# VocoreMotorShieldDRV8835.net
KiCad netlist of a schematic drawn in EAGLE
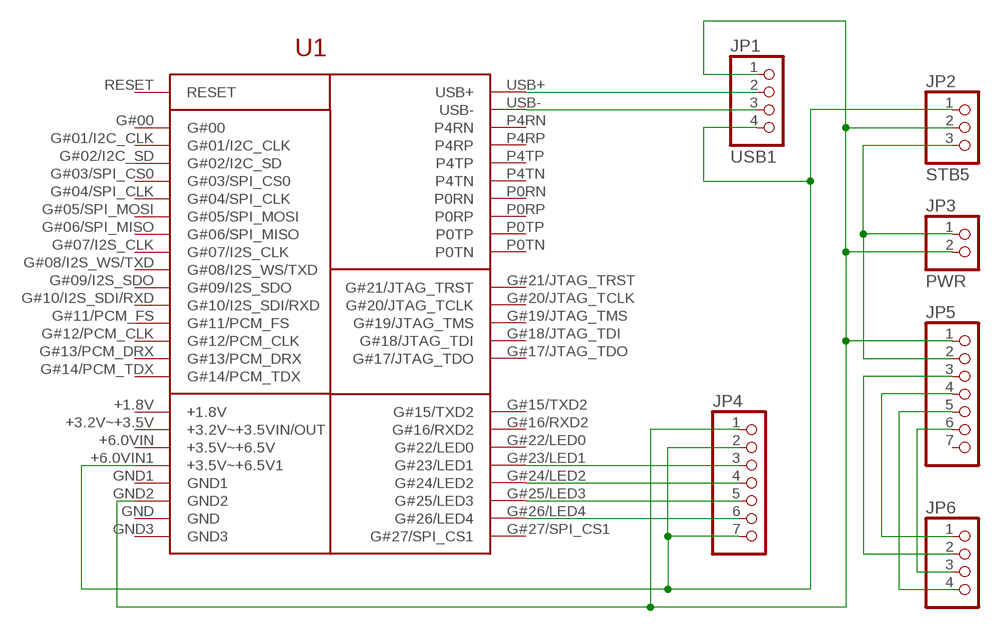
[diagram p0: schematic, sheet 1]

(export (version "E")
  (design (tool "Eeschema 10.0.6"))
  (components
    (comp (ref "JP1")
      (value "USB1")
      (footprint "eagle-import:1X04")
      (libsource (lib "eagle-import") (part "PINHD-1X4"))
    )
    (comp (ref "JP2")
      (value "STB5")
      (footprint "eagle-import:1X03")
      (libsource (lib "eagle-import") (part "PINHD-1X3"))
    )
    (comp (ref "JP3")
      (value "PWR")
      (footprint "eagle-import:1X02")
      (libsource (lib "eagle-import") (part "PINHD-1X2"))
    )
    (comp (ref "JP4")
      (value "PINHD-1X7")
      (footprint "eagle-import:1X07")
      (libsource (lib "eagle-import") (part "PINHD-1X7"))
    )
    (comp (ref "JP5")
      (value "PINHD-1X7")
      (footprint "eagle-import:1X07")
      (libsource (lib "eagle-import") (part "PINHD-1X7"))
    )
    (comp (ref "JP6")
      (value "PINHD-1X4")
      (footprint "eagle-import:1X04")
      (libsource (lib "eagle-import") (part "PINHD-1X4"))
    )
    (comp (ref "U1")
      (value "VOCORE_SHIELD")
      (footprint "eagle-import:VOCORE_DOC_CUSTOM")
      (libsource (lib "eagle-import") (part "VOCORE_SHIELD"))
    )
  )
  (nets
    (net (code "1") (name "Net-(JP1-Pad1)") (class "Default")
      (node (ref "JP1") (pin "1") (pinfunction "1_1") (pintype "passive"))
      (node (ref "JP2") (pin "2") (pinfunction "2_2") (pintype "passive"))
      (node (ref "JP3") (pin "2") (pinfunction "2_2") (pintype "passive"))
      (node (ref "JP4") (pin "1") (pinfunction "1_1") (pintype "passive"))
      (node (ref "JP5") (pin "1") (pinfunction "1_1") (pintype "passive"))
      (node (ref "U1") (pin "GND2") (pinfunction "GND2_GND2") (pintype "bidirectional"))
    )
    (net (code "2") (name "Net-(JP1-Pad2)") (class "Default")
      (node (ref "JP1") (pin "2") (pinfunction "2_2") (pintype "passive"))
      (node (ref "U1") (pin "USB+") (pinfunction "USB+_USB+") (pintype "bidirectional"))
    )
    (net (code "3") (name "Net-(JP1-Pad3)") (class "Default")
      (node (ref "JP1") (pin "3") (pinfunction "3_3") (pintype "passive"))
      (node (ref "U1") (pin "USB-") (pinfunction "USB-_USB-") (pintype "bidirectional"))
    )
    (net (code "4") (name "Net-(JP2-Pad3)") (class "Default")
      (node (ref "JP2") (pin "3") (pinfunction "3_3") (pintype "passive"))
      (node (ref "JP3") (pin "1") (pinfunction "1_1") (pintype "passive"))
      (node (ref "JP5") (pin "2") (pinfunction "2_2") (pintype "passive"))
    )
    (net (code "5") (name "Net-(JP4-Pad3)") (class "Default")
      (node (ref "JP4") (pin "3") (pinfunction "3_3") (pintype "passive"))
      (node (ref "U1") (pin "G#23/LED1") (pinfunction "G#23/LED1_G#23/LED1") (pintype "bidirectional"))
    )
    (net (code "6") (name "Net-(JP4-Pad4)") (class "Default")
      (node (ref "JP4") (pin "4") (pinfunction "4_4") (pintype "passive"))
      (node (ref "U1") (pin "G#24/LED2") (pinfunction "G#24/LED2_G#24/LED2") (pintype "bidirectional"))
    )
    (net (code "7") (name "Net-(JP4-Pad5)") (class "Default")
      (node (ref "JP4") (pin "5") (pinfunction "5_5") (pintype "passive"))
      (node (ref "U1") (pin "G#25/LED3") (pinfunction "G#25/LED3_G#25/LED3") (pintype "bidirectional"))
    )
    (net (code "8") (name "Net-(JP4-Pad6)") (class "Default")
      (node (ref "JP4") (pin "6") (pinfunction "6_6") (pintype "passive"))
      (node (ref "U1") (pin "G#26/LED4") (pinfunction "G#26/LED4_G#26/LED4") (pintype "bidirectional"))
    )
    (net (code "9") (name "Net-(JP5-Pad3)") (class "Default")
      (node (ref "JP5") (pin "3") (pinfunction "3_3") (pintype "passive"))
      (node (ref "JP6") (pin "2") (pinfunction "2_2") (pintype "passive"))
    )
    (net (code "10") (name "Net-(JP5-Pad4)") (class "Default")
      (node (ref "JP5") (pin "4") (pinfunction "4_4") (pintype "passive"))
      (node (ref "JP6") (pin "1") (pinfunction "1_1") (pintype "passive"))
    )
    (net (code "11") (name "Net-(JP5-Pad5)") (class "Default")
      (node (ref "JP5") (pin "5") (pinfunction "5_5") (pintype "passive"))
      (node (ref "JP6") (pin "4") (pinfunction "4_4") (pintype "passive"))
    )
    (net (code "12") (name "Net-(JP5-Pad6)") (class "Default")
      (node (ref "JP5") (pin "6") (pinfunction "6_6") (pintype "passive"))
      (node (ref "JP6") (pin "3") (pinfunction "3_3") (pintype "passive"))
    )
    (net (code "13") (name "Net-(U1-+3.5V~{+6.5V1})") (class "Default")
      (node (ref "JP1") (pin "4") (pinfunction "4_4") (pintype "passive"))
      (node (ref "JP2") (pin "1") (pinfunction "1_1") (pintype "passive"))
      (node (ref "JP4") (pin "2") (pinfunction "2_2") (pintype "passive"))
      (node (ref "JP4") (pin "7") (pinfunction "7_7") (pintype "passive"))
      (node (ref "U1") (pin "+6.0VIN1") (pinfunction "+3.5V~{+6.5V1}_+6.0VIN1") (pintype "bidirectional"))
    )
    (net (code "14") (name "unconnected-(JP5-Pad7)") (class "Default")
      (node (ref "JP5") (pin "7") (pinfunction "7_7") (pintype "passive"))
    )
    (net (code "15") (name "unconnected-(U1-+3.2V~{+3.5VIN{slash}OUT}-Pad+3.2V~+3.5V)") (class "Default")
      (node (ref "U1") (pin "+3.2V~+3.5V") (pinfunction "+3.2V~{+3.5VIN/OUT}_+3.2V~+3.5V") (pintype "bidirectional"))
    )
    (net (code "16") (name "unconnected-(U1-+3.5V~{+6.5V}-Pad+6.0VIN)") (class "Default")
      (node (ref "U1") (pin "+6.0VIN") (pinfunction "+3.5V~{+6.5V}_+6.0VIN") (pintype "bidirectional"))
    )
    (net (code "17") (name "unconnected-(U1-Pad+1.8V)") (class "Default")
      (node (ref "U1") (pin "+1.8V") (pinfunction "+1.8V_+1.8V") (pintype "bidirectional"))
    )
    (net (code "18") (name "unconnected-(U1-PadG#00)") (class "Default")
      (node (ref "U1") (pin "G#00") (pinfunction "G#00_G#00") (pintype "bidirectional"))
    )
    (net (code "19") (name "unconnected-(U1-PadG#01{slash}I2C_CLK)") (class "Default")
      (node (ref "U1") (pin "G#01/I2C_CLK") (pinfunction "G#01/I2C_CLK_G#01/I2C_CLK") (pintype "bidirectional"))
    )
    (net (code "20") (name "unconnected-(U1-PadG#02{slash}I2C_SD)") (class "Default")
      (node (ref "U1") (pin "G#02/I2C_SD") (pinfunction "G#02/I2C_SD_G#02/I2C_SD") (pintype "bidirectional"))
    )
    (net (code "21") (name "unconnected-(U1-PadG#03{slash}SPI_CS0)") (class "Default")
      (node (ref "U1") (pin "G#03/SPI_CS0") (pinfunction "G#03/SPI_CS0_G#03/SPI_CS0") (pintype "bidirectional"))
    )
    (net (code "22") (name "unconnected-(U1-PadG#04{slash}SPI_CLK)") (class "Default")
      (node (ref "U1") (pin "G#04/SPI_CLK") (pinfunction "G#04/SPI_CLK_G#04/SPI_CLK") (pintype "bidirectional"))
    )
    (net (code "23") (name "unconnected-(U1-PadG#05{slash}SPI_MOSI)") (class "Default")
      (node (ref "U1") (pin "G#05/SPI_MOSI") (pinfunction "G#05/SPI_MOSI_G#05/SPI_MOSI") (pintype "bidirectional"))
    )
    (net (code "24") (name "unconnected-(U1-PadG#06{slash}SPI_MISO)") (class "Default")
      (node (ref "U1") (pin "G#06/SPI_MISO") (pinfunction "G#06/SPI_MISO_G#06/SPI_MISO") (pintype "bidirectional"))
    )
    (net (code "25") (name "unconnected-(U1-PadG#07{slash}I2S_CLK)") (class "Default")
      (node (ref "U1") (pin "G#07/I2S_CLK") (pinfunction "G#07/I2S_CLK_G#07/I2S_CLK") (pintype "bidirectional"))
    )
    (net (code "26") (name "unconnected-(U1-PadG#08{slash}I2S_WS{slash}TXD)") (class "Default")
      (node (ref "U1") (pin "G#08/I2S_WS/TXD") (pinfunction "G#08/I2S_WS/TXD_G#08/I2S_WS/TXD") (pintype "bidirectional"))
    )
    (net (code "27") (name "unconnected-(U1-PadG#09{slash}I2S_SDO)") (class "Default")
      (node (ref "U1") (pin "G#09/I2S_SDO") (pinfunction "G#09/I2S_SDO_G#09/I2S_SDO") (pintype "bidirectional"))
    )
    (net (code "28") (name "unconnected-(U1-PadG#10{slash}I2S_SDI{slash}RXD)") (class "Default")
      (node (ref "U1") (pin "G#10/I2S_SDI/RXD") (pinfunction "G#10/I2S_SDI/RXD_G#10/I2S_SDI/RXD") (pintype "bidirectional"))
    )
    (net (code "29") (name "unconnected-(U1-PadG#11{slash}PCM_FS)") (class "Default")
      (node (ref "U1") (pin "G#11/PCM_FS") (pinfunction "G#11/PCM_FS_G#11/PCM_FS") (pintype "bidirectional"))
    )
    (net (code "30") (name "unconnected-(U1-PadG#12{slash}PCM_CLK)") (class "Default")
      (node (ref "U1") (pin "G#12/PCM_CLK") (pinfunction "G#12/PCM_CLK_G#12/PCM_CLK") (pintype "bidirectional"))
    )
    (net (code "31") (name "unconnected-(U1-PadG#13{slash}PCM_DRX)") (class "Default")
      (node (ref "U1") (pin "G#13/PCM_DRX") (pinfunction "G#13/PCM_DRX_G#13/PCM_DRX") (pintype "bidirectional"))
    )
    (net (code "32") (name "unconnected-(U1-PadG#14{slash}PCM_TDX)") (class "Default")
      (node (ref "U1") (pin "G#14/PCM_TDX") (pinfunction "G#14/PCM_TDX_G#14/PCM_TDX") (pintype "bidirectional"))
    )
    (net (code "33") (name "unconnected-(U1-PadG#15{slash}TXD2)") (class "Default")
      (node (ref "U1") (pin "G#15/TXD2") (pinfunction "G#15/TXD2_G#15/TXD2") (pintype "bidirectional"))
    )
    (net (code "34") (name "unconnected-(U1-PadG#16{slash}RXD2)") (class "Default")
      (node (ref "U1") (pin "G#16/RXD2") (pinfunction "G#16/RXD2_G#16/RXD2") (pintype "bidirectional"))
    )
    (net (code "35") (name "unconnected-(U1-PadG#17{slash}JTAG_TDO)") (class "Default")
      (node (ref "U1") (pin "G#17/JTAG_TDO") (pinfunction "G#17/JTAG_TDO_G#17/JTAG_TDO") (pintype "bidirectional"))
    )
    (net (code "36") (name "unconnected-(U1-PadG#18{slash}JTAG_TDI)") (class "Default")
      (node (ref "U1") (pin "G#18/JTAG_TDI") (pinfunction "G#18/JTAG_TDI_G#18/JTAG_TDI") (pintype "bidirectional"))
    )
    (net (code "37") (name "unconnected-(U1-PadG#19{slash}JTAG_TMS)") (class "Default")
      (node (ref "U1") (pin "G#19/JTAG_TMS") (pinfunction "G#19/JTAG_TMS_G#19/JTAG_TMS") (pintype "bidirectional"))
    )
    (net (code "38") (name "unconnected-(U1-PadG#20{slash}JTAG_TCLK)") (class "Default")
      (node (ref "U1") (pin "G#20/JTAG_TCLK") (pinfunction "G#20/JTAG_TCLK_G#20/JTAG_TCLK") (pintype "bidirectional"))
    )
    (net (code "39") (name "unconnected-(U1-PadG#21{slash}JTAG_TRST)") (class "Default")
      (node (ref "U1") (pin "G#21/JTAG_TRST") (pinfunction "G#21/JTAG_TRST_G#21/JTAG_TRST") (pintype "bidirectional"))
    )
    (net (code "40") (name "unconnected-(U1-PadG#22{slash}LED0)") (class "Default")
      (node (ref "U1") (pin "G#22/LED0") (pinfunction "G#22/LED0_G#22/LED0") (pintype "bidirectional"))
    )
    (net (code "41") (name "unconnected-(U1-PadG#27{slash}SPI_CS1)") (class "Default")
      (node (ref "U1") (pin "G#27/SPI_CS1") (pinfunction "G#27/SPI_CS1_G#27/SPI_CS1") (pintype "bidirectional"))
    )
    (net (code "42") (name "unconnected-(U1-PadGND)") (class "Default")
      (node (ref "U1") (pin "GND") (pinfunction "GND_GND") (pintype "bidirectional"))
    )
    (net (code "43") (name "unconnected-(U1-PadGND1)") (class "Default")
      (node (ref "U1") (pin "GND1") (pinfunction "GND1_GND1") (pintype "bidirectional"))
    )
    (net (code "44") (name "unconnected-(U1-PadGND3)") (class "Default")
      (node (ref "U1") (pin "GND3") (pinfunction "GND3_GND3") (pintype "bidirectional"))
    )
    (net (code "45") (name "unconnected-(U1-PadP0RN)") (class "Default")
      (node (ref "U1") (pin "P0RN") (pinfunction "P0RN_P0RN") (pintype "bidirectional"))
    )
    (net (code "46") (name "unconnected-(U1-PadP0RP)") (class "Default")
      (node (ref "U1") (pin "P0RP") (pinfunction "P0RP_P0RP") (pintype "bidirectional"))
    )
    (net (code "47") (name "unconnected-(U1-PadP0TN)") (class "Default")
      (node (ref "U1") (pin "P0TN") (pinfunction "P0TN_P0TN") (pintype "bidirectional"))
    )
    (net (code "48") (name "unconnected-(U1-PadP0TP)") (class "Default")
      (node (ref "U1") (pin "P0TP") (pinfunction "P0TP_P0TP") (pintype "bidirectional"))
    )
    (net (code "49") (name "unconnected-(U1-PadP4RN)") (class "Default")
      (node (ref "U1") (pin "P4RN") (pinfunction "P4RN_P4RN") (pintype "bidirectional"))
    )
    (net (code "50") (name "unconnected-(U1-PadP4RP)") (class "Default")
      (node (ref "U1") (pin "P4RP") (pinfunction "P4RP_P4RP") (pintype "bidirectional"))
    )
    (net (code "51") (name "unconnected-(U1-PadP4TN)") (class "Default")
      (node (ref "U1") (pin "P4TN") (pinfunction "P4TN_P4TN") (pintype "bidirectional"))
    )
    (net (code "52") (name "unconnected-(U1-PadP4TP)") (class "Default")
      (node (ref "U1") (pin "P4TP") (pinfunction "P4TP_P4TP") (pintype "bidirectional"))
    )
    (net (code "53") (name "unconnected-(U1-PadRESET)") (class "Default")
      (node (ref "U1") (pin "RESET") (pinfunction "RESET_RESET") (pintype "bidirectional"))
    )
  )
)
